# 08_USB_To_UART.net
KiCad netlist of a schematic drawn in Altium Designer
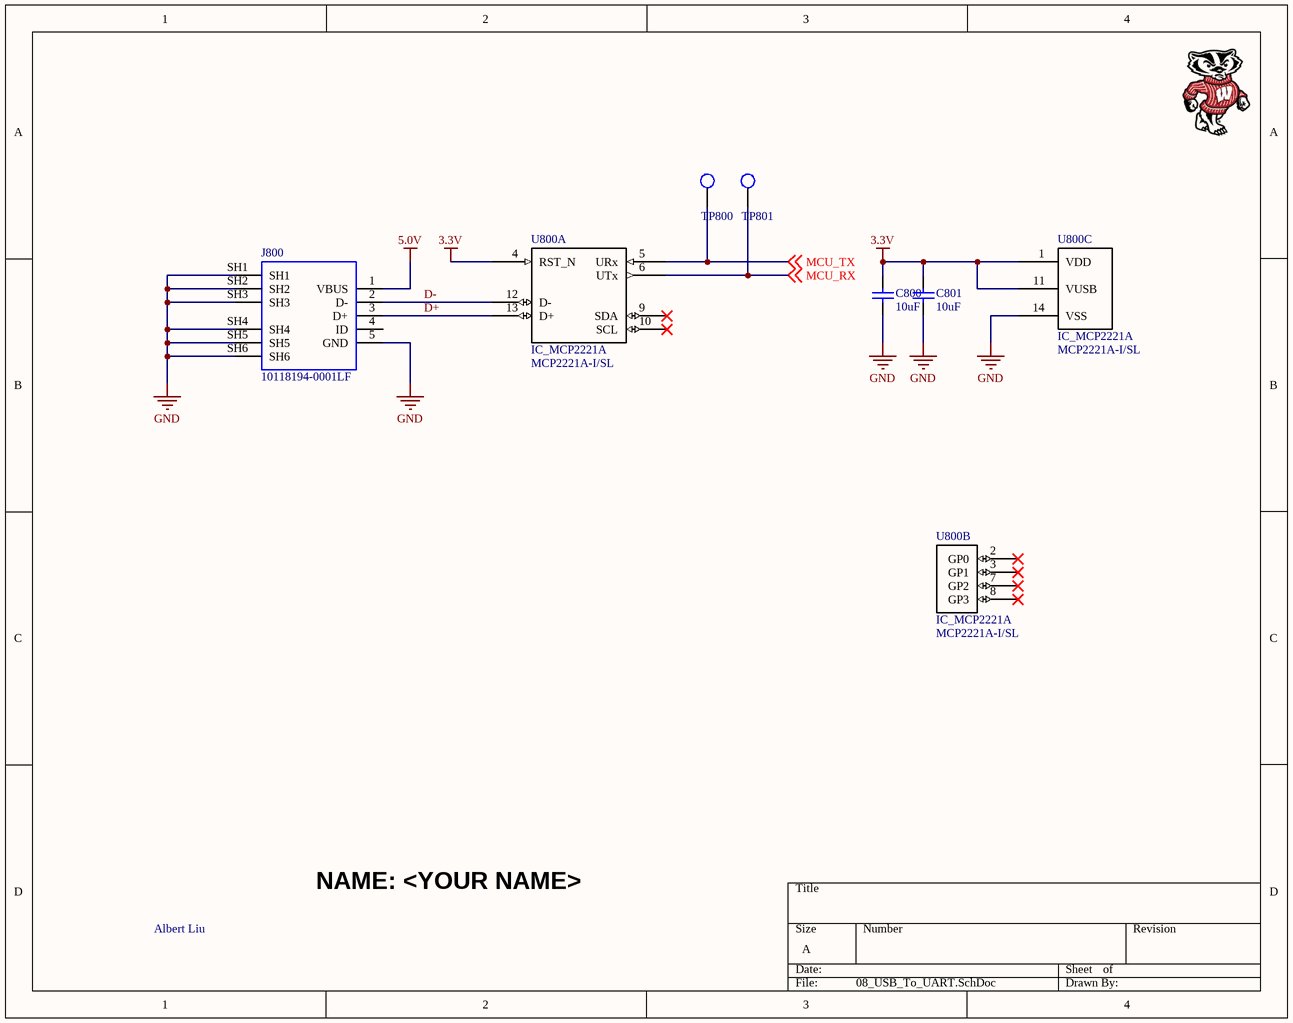
[diagram p0: 08_USB_To_UART.SchDoc]

(export (version "E")
  (design (tool "Eeschema 10.0.6"))
  (components
    (comp (ref "C800")
      (value "10uF")
      (footprint "CAP_0805")
      (description "CAP CER 10UF 16V X7R 0805")
      (fields
        (field (name "MANUFACTURER") "Samsung")
        (field (name "MANUFACTURER PART NUMBER") "CL21A106KPCLQNC")
        (field (name "CAPACITANCE") "10uF")
      )
      (libsource (lib "ece315-S20") (part "CAP_0805_U_010.00"))
    )
    (comp (ref "C801")
      (value "10uF")
      (footprint "CAP_0805")
      (description "CAP CER 10UF 16V X7R 0805")
      (fields
        (field (name "MANUFACTURER") "Samsung")
        (field (name "MANUFACTURER PART NUMBER") "CL21A106KPCLQNC")
        (field (name "CAPACITANCE") "10uF")
      )
      (libsource (lib "ece315-S20") (part "CAP_0805_U_010.00"))
    )
    (comp (ref "J800")
      (value "USB_MICRO_B_10118194-0001LF")
      (footprint "USB_MICRO_B")
      (description "CONN USB MICRO B RECPT SMT R/A")
      (fields
        (field (name "MANUFACTURER") "Amphenol FCI")
        (field (name "MANUFACTURER PART NUMBER") "10118194-0001LF")
      )
      (libsource (lib "ece315-S20") (part "USB_MICRO_B_10118194-0001LF"))
    )
    (comp (ref "TP800")
      (value "TP_1206")
      (footprint "TP-SMC-1206")
      (description "Test Point SMD 1206")
      (fields
        (field (name "MANUFACTURER") "TE Connectivity (Tyco Electronics)")
        (field (name "MANUFACTURER PART NUMBER") "1625854-1")
      )
      (libsource (lib "ece315-S20") (part "TP_1206"))
    )
    (comp (ref "TP801")
      (value "TP_1206")
      (footprint "TP-SMC-1206")
      (description "Test Point SMD 1206")
      (fields
        (field (name "MANUFACTURER") "TE Connectivity (Tyco Electronics)")
        (field (name "MANUFACTURER PART NUMBER") "1625854-1")
      )
      (libsource (lib "ece315-S20") (part "TP_1206"))
    )
    (comp (ref "U800")
      (value "IC_MCP2221A")
      (footprint "IC_MCP2221A")
      (description "IC USB TO I2C/UART 14SOIC")
      (fields
        (field (name "MANUFACTURER") "Microchip")
        (field (name "MANUFACTURER PART NUMBER") "MCP2221A-I/SL")
      )
      (libsource (lib "ece315-S20") (part "IC_MCP2221A"))
    )
  )
  (nets
    (net (code "1") (name "/D+") (class "Default")
      (node (ref "J800") (pin "3") (pinfunction "D+_3") (pintype "passive"))
      (node (ref "U800") (pin "13") (pinfunction "D+_13") (pintype "bidirectional"))
    )
    (net (code "2") (name "/D-") (class "Default")
      (node (ref "J800") (pin "2") (pinfunction "D-_2") (pintype "passive"))
      (node (ref "U800") (pin "12") (pinfunction "D-_12") (pintype "bidirectional"))
    )
    (net (code "3") (name "3.3V") (class "Default")
      (node (ref "C800") (pin "2") (pinfunction "2_2") (pintype "passive"))
      (node (ref "C801") (pin "2") (pinfunction "2_2") (pintype "passive"))
      (node (ref "U800") (pin "1") (pinfunction "VDD_1") (pintype "power_in"))
      (node (ref "U800") (pin "11") (pinfunction "VUSB_11") (pintype "power_in"))
      (node (ref "U800") (pin "4") (pinfunction "RST_N_4") (pintype "input"))
    )
    (net (code "4") (name "5.0V") (class "Default")
      (node (ref "J800") (pin "1") (pinfunction "VBUS_1") (pintype "passive"))
    )
    (net (code "5") (name "GND") (class "Default")
      (node (ref "C800") (pin "1") (pinfunction "1_1") (pintype "passive"))
      (node (ref "C801") (pin "1") (pinfunction "1_1") (pintype "passive"))
      (node (ref "J800") (pin "5") (pinfunction "GND_5") (pintype "passive"))
      (node (ref "J800") (pin "SH1") (pinfunction "SH1_SH1") (pintype "passive"))
      (node (ref "J800") (pin "SH2") (pinfunction "SH2_SH2") (pintype "passive"))
      (node (ref "J800") (pin "SH3") (pinfunction "SH3_SH3") (pintype "passive"))
      (node (ref "J800") (pin "SH4") (pinfunction "SH4_SH4") (pintype "passive"))
      (node (ref "J800") (pin "SH5") (pinfunction "SH5_SH5") (pintype "passive"))
      (node (ref "J800") (pin "SH6") (pinfunction "SH6_SH6") (pintype "passive"))
      (node (ref "U800") (pin "14") (pinfunction "VSS_14") (pintype "power_in"))
    )
    (net (code "6") (name "MCU_RX") (class "Default")
      (node (ref "TP801") (pin "1") (pintype "passive"))
      (node (ref "U800") (pin "6") (pinfunction "UTx_6") (pintype "output"))
    )
    (net (code "7") (name "MCU_TX") (class "Default")
      (node (ref "TP800") (pin "1") (pintype "passive"))
      (node (ref "U800") (pin "5") (pinfunction "URx_5") (pintype "input"))
    )
    (net (code "8") (name "unconnected-(J800-ID-Pad4)") (class "Default")
      (node (ref "J800") (pin "4") (pinfunction "ID_4") (pintype "passive"))
    )
    (net (code "9") (name "unconnected-(U800A-SCL-Pad10)") (class "Default")
      (node (ref "U800") (pin "10") (pinfunction "SCL_10") (pintype "bidirectional+no_connect"))
    )
    (net (code "10") (name "unconnected-(U800A-SDA-Pad9)") (class "Default")
      (node (ref "U800") (pin "9") (pinfunction "SDA_9") (pintype "bidirectional+no_connect"))
    )
    (net (code "11") (name "unconnected-(U800B-GP0-Pad2)") (class "Default")
      (node (ref "U800") (pin "2") (pinfunction "GP0_2") (pintype "bidirectional+no_connect"))
    )
    (net (code "12") (name "unconnected-(U800B-GP1-Pad3)") (class "Default")
      (node (ref "U800") (pin "3") (pinfunction "GP1_3") (pintype "bidirectional+no_connect"))
    )
    (net (code "13") (name "unconnected-(U800B-GP2-Pad7)") (class "Default")
      (node (ref "U800") (pin "7") (pinfunction "GP2_7") (pintype "bidirectional+no_connect"))
    )
    (net (code "14") (name "unconnected-(U800B-GP3-Pad8)") (class "Default")
      (node (ref "U800") (pin "8") (pinfunction "GP3_8") (pintype "bidirectional+no_connect"))
    )
  )
)
